# satshakit_cnc.net
KiCad netlist of a schematic drawn in EAGLE
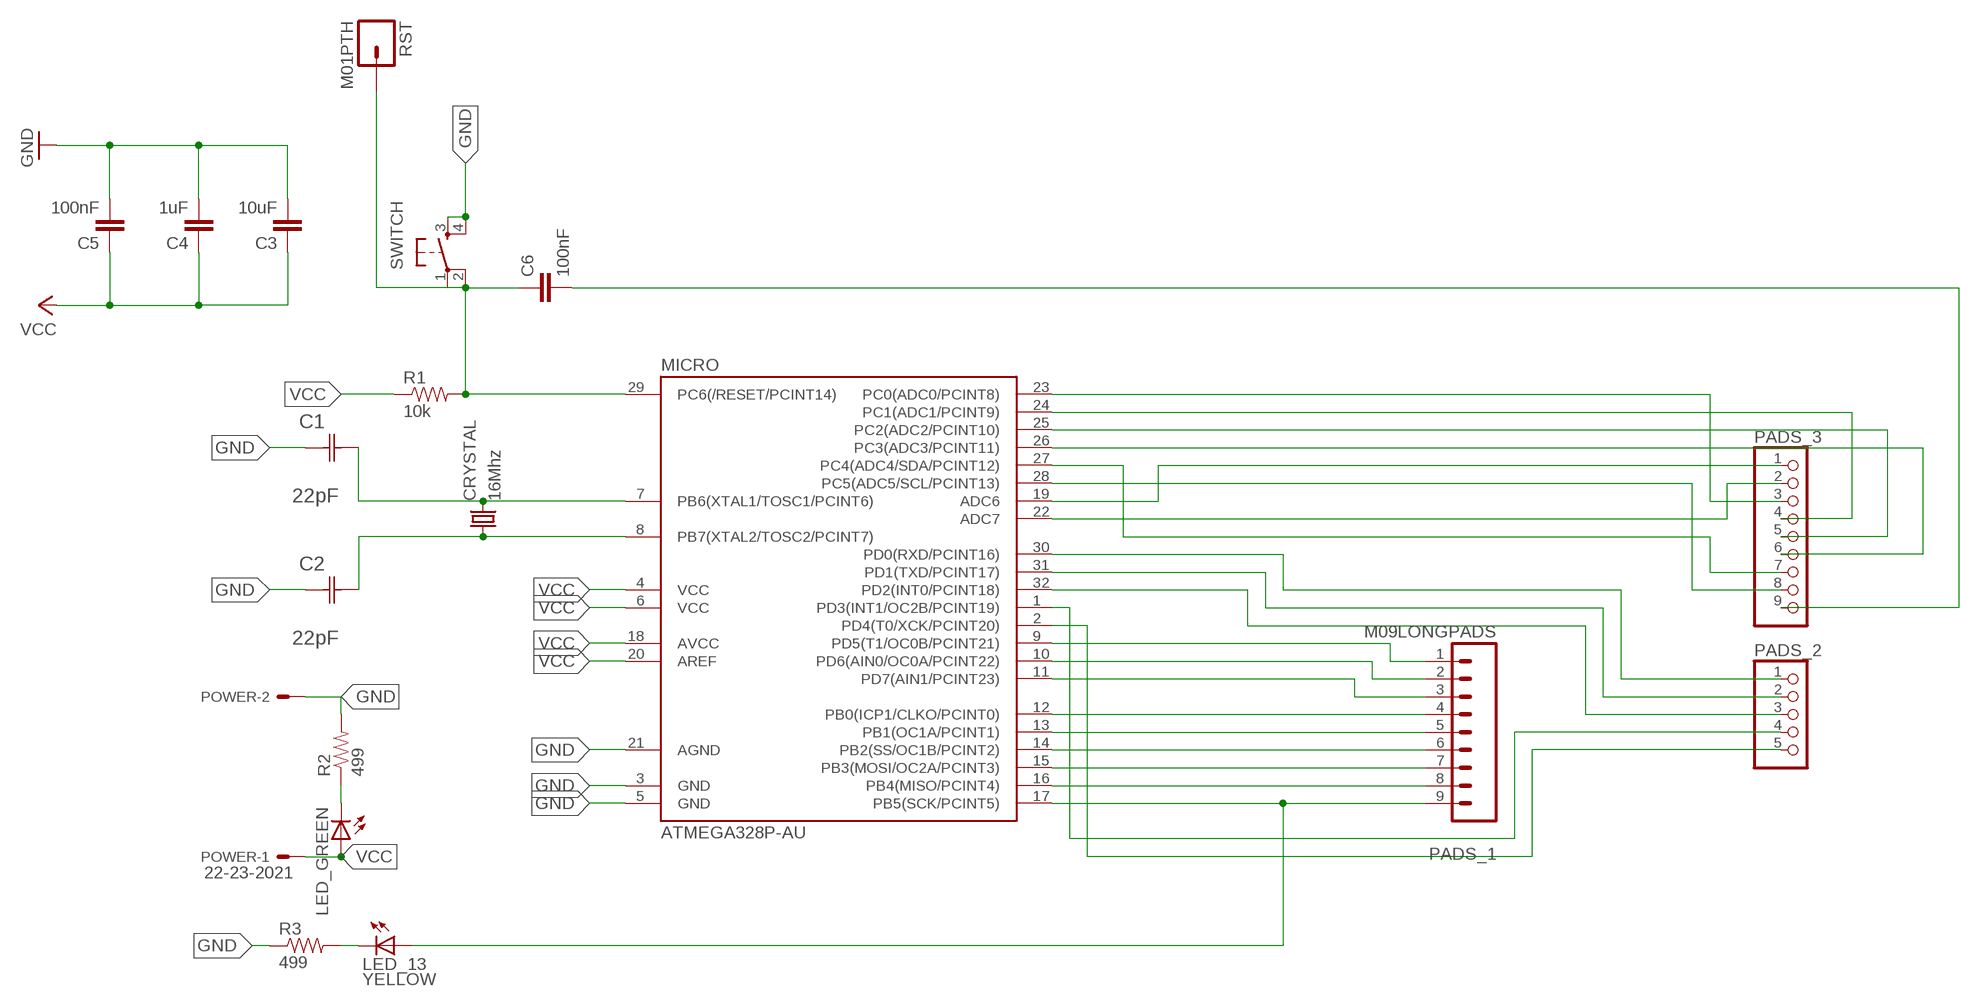
[diagram p0: schematic, sheet 1]

(export (version "E")
  (design (tool "Eeschema 10.0.6"))
  (components
    (comp (ref "C1")
      (value "22pF")
      (footprint "eagle-import:CAPC3216X178N")
      (fields (field (name "MPN") "0612ZC225MAT2A") (field (name "TOLERANCE") "±20%"))
      (libsource (lib "eagle-import") (part "0612ZC225MAT2A"))
    )
    (comp (ref "C2")
      (value "22pF")
      (footprint "eagle-import:CAPC3216X178N")
      (fields (field (name "MPN") "0612ZC225MAT2A") (field (name "TOLERANCE") "±20%"))
      (libsource (lib "eagle-import") (part "0612ZC225MAT2A"))
    )
    (comp (ref "C3")
      (value "10uF")
      (footprint "eagle-import:1206")
      (libsource (lib "eagle-import") (part "CAP1206"))
    )
    (comp (ref "C4")
      (value "1uF")
      (footprint "eagle-import:1206")
      (libsource (lib "eagle-import") (part "CAP1206"))
    )
    (comp (ref "C5")
      (value "100nF")
      (footprint "eagle-import:1206")
      (libsource (lib "eagle-import") (part "CAP1206"))
    )
    (comp (ref "C6")
      (value "100nF")
      (footprint "eagle-import:1206")
      (libsource (lib "eagle-import") (part "CAP1206"))
    )
    (comp (ref "CRYSTAL")
      (value "16Mhz")
      (footprint "eagle-import:CSM-7X-DU")
      (libsource (lib "eagle-import") (part "CSM-7X-DU"))
    )
    (comp (ref "LED_13")
      (value "YELLOW")
      (footprint "eagle-import:1206")
      (libsource (lib "eagle-import") (part "LED1206"))
    )
    (comp (ref "LED_GREEN")
      (value "LED1206")
      (footprint "eagle-import:1206")
      (libsource (lib "eagle-import") (part "LED1206"))
    )
    (comp (ref "MICRO")
      (value "ATMEGA328P-AU")
      (footprint "eagle-import:TQFP32-08")
      (libsource (lib "eagle-import") (part "ATMEGA48/88/168-AU"))
    )
    (comp (ref "PADS_1")
      (value "M09LONGPADS")
      (footprint "eagle-import:1X09_LONGPADS")
      (libsource (lib "eagle-import") (part "M09LONGPADS"))
    )
    (comp (ref "PADS_2")
      (value "PINHD-1X5")
      (footprint "eagle-import:1X05")
      (libsource (lib "eagle-import") (part "PINHD-1X5"))
    )
    (comp (ref "PADS_3")
      (value "PINHD-1X9")
      (footprint "eagle-import:1X09")
      (libsource (lib "eagle-import") (part "PINHD-1X9"))
    )
    (comp (ref "POWER")
      (value "22-23-2021")
      (footprint "eagle-import:22-23-2021")
      (fields (field (name "MF") "MOLEX"))
      (libsource (lib "eagle-import") (part "22-23-2021"))
    )
    (comp (ref "R1")
      (value "10k")
      (footprint "eagle-import:1206")
      (libsource (lib "eagle-import") (part "RESISTOR1206"))
    )
    (comp (ref "R2")
      (value "499")
      (footprint "eagle-import:1206")
      (libsource (lib "eagle-import") (part "RESISTOR1206"))
    )
    (comp (ref "R3")
      (value "499")
      (footprint "eagle-import:1206")
      (libsource (lib "eagle-import") (part "RESISTOR1206"))
    )
    (comp (ref "RST")
      (value "M01PTH")
      (footprint "eagle-import:1X01")
      (libsource (lib "eagle-import") (part "M01PTH"))
    )
    (comp (ref "SWITCH")
      (value "6MM_SWITCH6MM_SWITCH")
      (footprint "eagle-import:6MM_SWITCH")
      (libsource (lib "eagle-import") (part "6MM_SWITCH6MM_SWITCH"))
    )
  )
  (nets
    (net (code "1") (name "GND") (class "Default")
      (node (ref "C1") (pin "1") (pinfunction "C1_1") (pintype "passive"))
      (node (ref "C2") (pin "1") (pinfunction "C1_1") (pintype "passive"))
      (node (ref "C3") (pin "2") (pinfunction "2_2") (pintype "passive"))
      (node (ref "C4") (pin "2") (pinfunction "2_2") (pintype "passive"))
      (node (ref "C5") (pin "2") (pinfunction "2_2") (pintype "passive"))
      (node (ref "MICRO") (pin "21") (pinfunction "AGND_21") (pintype "power_in"))
      (node (ref "MICRO") (pin "3") (pinfunction "GND_3") (pintype "power_in"))
      (node (ref "MICRO") (pin "5") (pinfunction "GND_5") (pintype "power_in"))
      (node (ref "POWER") (pin "2") (pinfunction "S_2") (pintype "passive"))
      (node (ref "R2") (pin "2") (pinfunction "2_2") (pintype "passive"))
      (node (ref "R3") (pin "1") (pinfunction "1_1") (pintype "passive"))
      (node (ref "SWITCH") (pin "3") (pinfunction "S_3") (pintype "passive"))
      (node (ref "SWITCH") (pin "4") (pinfunction "S1_4") (pintype "passive"))
    )
    (net (code "2") (name "Net-(C1-C2)") (class "Default")
      (node (ref "C1") (pin "2") (pinfunction "C2_2") (pintype "passive"))
      (node (ref "CRYSTAL") (pin "2") (pinfunction "2_2") (pintype "passive"))
      (node (ref "MICRO") (pin "7") (pinfunction "PB6(XTAL1/TOSC1/PCINT6)_7") (pintype "bidirectional"))
    )
    (net (code "3") (name "Net-(C2-C2)") (class "Default")
      (node (ref "C2") (pin "2") (pinfunction "C2_2") (pintype "passive"))
      (node (ref "CRYSTAL") (pin "1") (pinfunction "1_1") (pintype "passive"))
      (node (ref "MICRO") (pin "8") (pinfunction "PB7(XTAL2/TOSC2/PCINT7)_8") (pintype "bidirectional"))
    )
    (net (code "4") (name "Net-(C6-Pad2)") (class "Default")
      (node (ref "C6") (pin "2") (pinfunction "2_2") (pintype "passive"))
      (node (ref "PADS_3") (pin "9") (pinfunction "9_9") (pintype "passive"))
    )
    (net (code "5") (name "Net-(LED_13-A)") (class "Default")
      (node (ref "LED_13") (pin "1") (pinfunction "A_1") (pintype "passive"))
      (node (ref "MICRO") (pin "17") (pinfunction "PB5(SCK/PCINT5)_17") (pintype "bidirectional"))
      (node (ref "PADS_1") (pin "9") (pinfunction "9_9") (pintype "passive"))
    )
    (net (code "6") (name "Net-(LED_13-C)") (class "Default")
      (node (ref "LED_13") (pin "2") (pinfunction "C_2") (pintype "passive"))
      (node (ref "R3") (pin "2") (pinfunction "2_2") (pintype "passive"))
    )
    (net (code "7") (name "Net-(LED_GREEN-C)") (class "Default")
      (node (ref "LED_GREEN") (pin "2") (pinfunction "C_2") (pintype "passive"))
      (node (ref "R2") (pin "1") (pinfunction "1_1") (pintype "passive"))
    )
    (net (code "8") (name "Net-(MICRO-ADC6)") (class "Default")
      (node (ref "MICRO") (pin "19") (pinfunction "ADC6_19") (pintype "passive"))
      (node (ref "PADS_3") (pin "1") (pinfunction "1_1") (pintype "passive"))
    )
    (net (code "9") (name "Net-(MICRO-ADC7)") (class "Default")
      (node (ref "MICRO") (pin "22") (pinfunction "ADC7_22") (pintype "passive"))
      (node (ref "PADS_3") (pin "2") (pinfunction "2_2") (pintype "passive"))
    )
    (net (code "10") (name "Net-(MICRO-PB0(ICP1{slash}CLKO{slash}PCINT0))") (class "Default")
      (node (ref "MICRO") (pin "12") (pinfunction "PB0(ICP1/CLKO/PCINT0)_12") (pintype "bidirectional"))
      (node (ref "PADS_1") (pin "4") (pinfunction "4_4") (pintype "passive"))
    )
    (net (code "11") (name "Net-(MICRO-PB1(OC1A{slash}PCINT1))") (class "Default")
      (node (ref "MICRO") (pin "13") (pinfunction "PB1(OC1A/PCINT1)_13") (pintype "bidirectional"))
      (node (ref "PADS_1") (pin "5") (pinfunction "5_5") (pintype "passive"))
    )
    (net (code "12") (name "Net-(MICRO-PB2(SS{slash}OC1B{slash}PCINT2))") (class "Default")
      (node (ref "MICRO") (pin "14") (pinfunction "PB2(SS/OC1B/PCINT2)_14") (pintype "bidirectional"))
      (node (ref "PADS_1") (pin "6") (pinfunction "6_6") (pintype "passive"))
    )
    (net (code "13") (name "Net-(MICRO-PB3(MOSI{slash}OC2A{slash}PCINT3))") (class "Default")
      (node (ref "MICRO") (pin "15") (pinfunction "PB3(MOSI/OC2A/PCINT3)_15") (pintype "bidirectional"))
      (node (ref "PADS_1") (pin "7") (pinfunction "7_7") (pintype "passive"))
    )
    (net (code "14") (name "Net-(MICRO-PB4(MISO{slash}PCINT4))") (class "Default")
      (node (ref "MICRO") (pin "16") (pinfunction "PB4(MISO/PCINT4)_16") (pintype "bidirectional"))
      (node (ref "PADS_1") (pin "8") (pinfunction "8_8") (pintype "passive"))
    )
    (net (code "15") (name "Net-(MICRO-PC0(ADC0{slash}PCINT8))") (class "Default")
      (node (ref "MICRO") (pin "23") (pinfunction "PC0(ADC0/PCINT8)_23") (pintype "bidirectional"))
      (node (ref "PADS_3") (pin "3") (pinfunction "3_3") (pintype "passive"))
    )
    (net (code "16") (name "Net-(MICRO-PC1(ADC1{slash}PCINT9))") (class "Default")
      (node (ref "MICRO") (pin "24") (pinfunction "PC1(ADC1/PCINT9)_24") (pintype "bidirectional"))
      (node (ref "PADS_3") (pin "4") (pinfunction "4_4") (pintype "passive"))
    )
    (net (code "17") (name "Net-(MICRO-PC2(ADC2{slash}PCINT10))") (class "Default")
      (node (ref "MICRO") (pin "25") (pinfunction "PC2(ADC2/PCINT10)_25") (pintype "bidirectional"))
      (node (ref "PADS_3") (pin "5") (pinfunction "5_5") (pintype "passive"))
    )
    (net (code "18") (name "Net-(MICRO-PC3(ADC3{slash}PCINT11))") (class "Default")
      (node (ref "MICRO") (pin "26") (pinfunction "PC3(ADC3/PCINT11)_26") (pintype "bidirectional"))
      (node (ref "PADS_3") (pin "6") (pinfunction "6_6") (pintype "passive"))
    )
    (net (code "19") (name "Net-(MICRO-PC4(ADC4{slash}SDA{slash}PCINT12))") (class "Default")
      (node (ref "MICRO") (pin "27") (pinfunction "PC4(ADC4/SDA/PCINT12)_27") (pintype "bidirectional"))
      (node (ref "PADS_3") (pin "7") (pinfunction "7_7") (pintype "passive"))
    )
    (net (code "20") (name "Net-(MICRO-PC5(ADC5{slash}SCL{slash}PCINT13))") (class "Default")
      (node (ref "MICRO") (pin "28") (pinfunction "PC5(ADC5/SCL/PCINT13)_28") (pintype "bidirectional"))
      (node (ref "PADS_3") (pin "8") (pinfunction "8_8") (pintype "passive"))
    )
    (net (code "21") (name "Net-(MICRO-PC6({slash}RESET{slash}PCINT14))") (class "Default")
      (node (ref "C6") (pin "1") (pinfunction "1_1") (pintype "passive"))
      (node (ref "MICRO") (pin "29") (pinfunction "PC6(/RESET/PCINT14)_29") (pintype "bidirectional"))
      (node (ref "R1") (pin "2") (pinfunction "2_2") (pintype "passive"))
      (node (ref "RST") (pin "1") (pinfunction "1_1") (pintype "passive"))
      (node (ref "SWITCH") (pin "1") (pinfunction "P_1") (pintype "passive"))
      (node (ref "SWITCH") (pin "2") (pinfunction "P1_2") (pintype "passive"))
    )
    (net (code "22") (name "Net-(MICRO-PD0(RXD{slash}PCINT16))") (class "Default")
      (node (ref "MICRO") (pin "30") (pinfunction "PD0(RXD/PCINT16)_30") (pintype "bidirectional"))
      (node (ref "PADS_2") (pin "1") (pinfunction "1_1") (pintype "passive"))
    )
    (net (code "23") (name "Net-(MICRO-PD1(TXD{slash}PCINT17))") (class "Default")
      (node (ref "MICRO") (pin "31") (pinfunction "PD1(TXD/PCINT17)_31") (pintype "bidirectional"))
      (node (ref "PADS_2") (pin "2") (pinfunction "2_2") (pintype "passive"))
    )
    (net (code "24") (name "Net-(MICRO-PD2(INT0{slash}PCINT18))") (class "Default")
      (node (ref "MICRO") (pin "32") (pinfunction "PD2(INT0/PCINT18)_32") (pintype "bidirectional"))
      (node (ref "PADS_2") (pin "3") (pinfunction "3_3") (pintype "passive"))
    )
    (net (code "25") (name "Net-(MICRO-PD3(INT1{slash}OC2B{slash}PCINT19))") (class "Default")
      (node (ref "MICRO") (pin "1") (pinfunction "PD3(INT1/OC2B/PCINT19)_1") (pintype "bidirectional"))
      (node (ref "PADS_2") (pin "4") (pinfunction "4_4") (pintype "passive"))
    )
    (net (code "26") (name "Net-(MICRO-PD4(T0{slash}XCK{slash}PCINT20))") (class "Default")
      (node (ref "MICRO") (pin "2") (pinfunction "PD4(T0/XCK/PCINT20)_2") (pintype "bidirectional"))
      (node (ref "PADS_2") (pin "5") (pinfunction "5_5") (pintype "passive"))
    )
    (net (code "27") (name "Net-(MICRO-PD5(T1{slash}OC0B{slash}PCINT21))") (class "Default")
      (node (ref "MICRO") (pin "9") (pinfunction "PD5(T1/OC0B/PCINT21)_9") (pintype "bidirectional"))
      (node (ref "PADS_1") (pin "1") (pinfunction "1_1") (pintype "passive"))
    )
    (net (code "28") (name "Net-(MICRO-PD6(AIN0{slash}OC0A{slash}PCINT22))") (class "Default")
      (node (ref "MICRO") (pin "10") (pinfunction "PD6(AIN0/OC0A/PCINT22)_10") (pintype "bidirectional"))
      (node (ref "PADS_1") (pin "2") (pinfunction "2_2") (pintype "passive"))
    )
    (net (code "29") (name "Net-(MICRO-PD7(AIN1{slash}PCINT23))") (class "Default")
      (node (ref "MICRO") (pin "11") (pinfunction "PD7(AIN1/PCINT23)_11") (pintype "bidirectional"))
      (node (ref "PADS_1") (pin "3") (pinfunction "3_3") (pintype "passive"))
    )
    (net (code "30") (name "VCC") (class "Default")
      (node (ref "C3") (pin "1") (pinfunction "1_1") (pintype "passive"))
      (node (ref "C4") (pin "1") (pinfunction "1_1") (pintype "passive"))
      (node (ref "C5") (pin "1") (pinfunction "1_1") (pintype "passive"))
      (node (ref "LED_GREEN") (pin "1") (pinfunction "A_1") (pintype "passive"))
      (node (ref "MICRO") (pin "18") (pinfunction "AVCC_18") (pintype "passive"))
      (node (ref "MICRO") (pin "20") (pinfunction "AREF_20") (pintype "passive"))
      (node (ref "MICRO") (pin "4") (pinfunction "VCC_4") (pintype "power_in"))
      (node (ref "MICRO") (pin "6") (pinfunction "VCC_6") (pintype "power_in"))
      (node (ref "POWER") (pin "1") (pinfunction "S_1") (pintype "passive"))
      (node (ref "R1") (pin "1") (pinfunction "1_1") (pintype "passive"))
    )
  )
)
